# Schematic.net
KiCad netlist of a schematic drawn in EAGLE
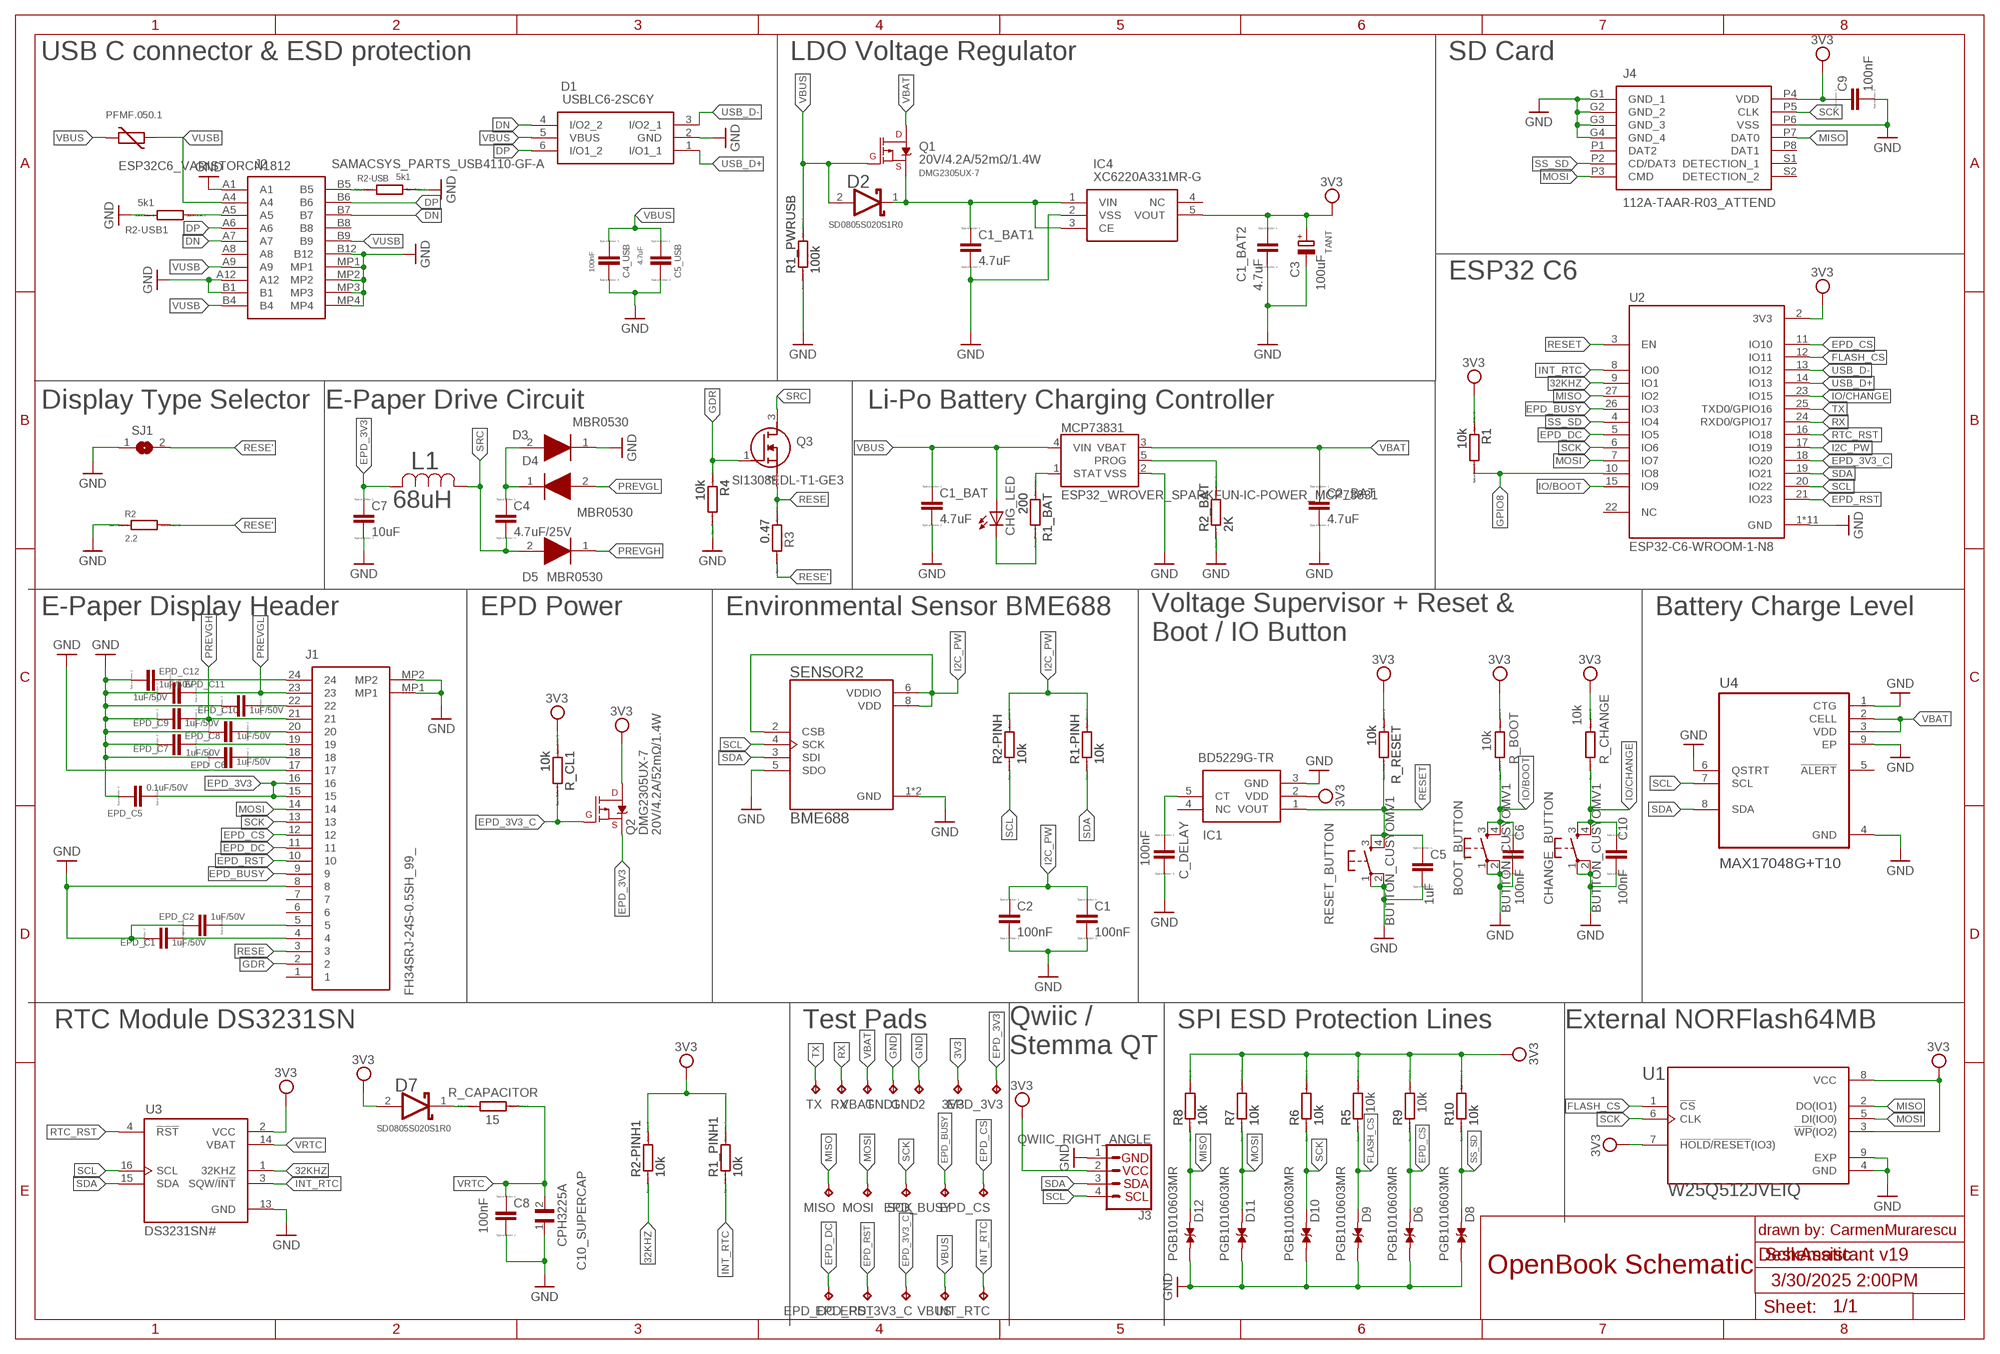
[diagram p0: schematic, sheet 1]

(export (version "E")
  (design (tool "Eeschema 10.0.6"))
  (components
    (comp (ref "3V3")
      (value "TPTP20R")
      (footprint "eagle-import:TP20R")
      (libsource (lib "eagle-import") (part "TPTP20R"))
    )
    (comp (ref "BOOT_BUTTON")
      (value "BUTTON_CUSYOMV1")
      (footprint "eagle-import:MYBUTTON")
      (libsource (lib "eagle-import") (part "BUTTON_CUSYOMV1"))
    )
    (comp (ref "C1")
      (value "100nF")
      (footprint "eagle-import:ESP32_WROVER_EAGLE-LTSPICE_C0402")
      (libsource (lib "eagle-import") (part "EAGLE-LTSPICE_CC0402"))
    )
    (comp (ref "C1_BAT")
      (value "4.7uF")
      (footprint "eagle-import:ESP32_WROVER_EAGLE-LTSPICE_C0402")
      (libsource (lib "eagle-import") (part "EAGLE-LTSPICE_CC0402"))
    )
    (comp (ref "C1_BAT1")
      (value "4.7uF")
      (footprint "eagle-import:ESP32_WROVER_EAGLE-LTSPICE_C0402")
      (libsource (lib "eagle-import") (part "ESP32_WROVER_EAGLE-LTSPICE_CC0402"))
    )
    (comp (ref "C1_BAT2")
      (value "4.7uF")
      (footprint "eagle-import:ESP32_WROVER_EAGLE-LTSPICE_C0402")
      (libsource (lib "eagle-import") (part "ESP32_WROVER_EAGLE-LTSPICE_CC0402"))
    )
    (comp (ref "C2")
      (value "100nF")
      (footprint "eagle-import:ESP32_WROVER_EAGLE-LTSPICE_C0402")
      (libsource (lib "eagle-import") (part "EAGLE-LTSPICE_CC0402"))
    )
    (comp (ref "C2_BAT")
      (value "4.7uF")
      (footprint "eagle-import:ESP32_WROVER_EAGLE-LTSPICE_C0402")
      (libsource (lib "eagle-import") (part "ESP32_WROVER_EAGLE-LTSPICE_CC0402"))
    )
    (comp (ref "C3")
      (value "100uF")
      (footprint "eagle-import:RCL_CT3528")
      (libsource (lib "eagle-import") (part "RCL_CPOL-EUCT3528"))
    )
    (comp (ref "C4")
      (value "4.7uF/25V")
      (footprint "eagle-import:ESP32_WROVER_EAGLE-LTSPICE_C0402")
      (libsource (lib "eagle-import") (part "EAGLE-LTSPICE_CC0402"))
    )
    (comp (ref "C4_USB")
      (value "100nF")
      (footprint "eagle-import:ESP32_WROVER_EAGLE-LTSPICE_C0402")
      (libsource (lib "eagle-import") (part "ESP32_WROVER_EAGLE-LTSPICE_CC0402"))
    )
    (comp (ref "C5")
      (value "1uF")
      (footprint "eagle-import:ESP32_WROVER_EAGLE-LTSPICE_C0402")
      (libsource (lib "eagle-import") (part "EAGLE-LTSPICE_CC0402"))
    )
    (comp (ref "C5_USB")
      (value "4.7uF")
      (footprint "eagle-import:ESP32_WROVER_EAGLE-LTSPICE_C0402")
      (libsource (lib "eagle-import") (part "ESP32_WROVER_EAGLE-LTSPICE_CC0402"))
    )
    (comp (ref "C6")
      (value "100nF")
      (footprint "eagle-import:ESP32_WROVER_EAGLE-LTSPICE_C0402")
      (libsource (lib "eagle-import") (part "ESP32_WROVER_EAGLE-LTSPICE_CC0402"))
    )
    (comp (ref "C7")
      (value "10uF")
      (footprint "eagle-import:ESP32_WROVER_EAGLE-LTSPICE_C0402")
      (libsource (lib "eagle-import") (part "ESP32_WROVER_EAGLE-LTSPICE_CC0402"))
    )
    (comp (ref "C8")
      (value "100nF")
      (footprint "eagle-import:ESP32_WROVER_EAGLE-LTSPICE_C0402")
      (libsource (lib "eagle-import") (part "ESP32_WROVER_EAGLE-LTSPICE_CC0402"))
    )
    (comp (ref "C9")
      (value "100nF")
      (footprint "eagle-import:ESP32_WROVER_EAGLE-LTSPICE_C0402")
      (libsource (lib "eagle-import") (part "EAGLE-LTSPICE_CC0402"))
    )
    (comp (ref "C10")
      (value "100nF")
      (footprint "eagle-import:ESP32_WROVER_EAGLE-LTSPICE_C0402")
      (libsource (lib "eagle-import") (part "ESP32_WROVER_EAGLE-LTSPICE_CC0402"))
    )
    (comp (ref "C10_SUPERCAP")
      (value "CPH3225A")
      (footprint "eagle-import:CAPCP3225X100N")
      (fields (field (name "MF") "Seiko Instruments"))
      (libsource (lib "eagle-import") (part "CPH3225A"))
    )
    (comp (ref "CHANGE_BUTTON")
      (value "BUTTON_CUSYOMV1")
      (footprint "eagle-import:MYBUTTON")
      (libsource (lib "eagle-import") (part "BUTTON_CUSYOMV1"))
    )
    (comp (ref "CHG_LED")
      (value "ADAFRUIT_LEDCHIP-LED0603")
      (footprint "eagle-import:ADAFRUIT_CHIP-LED0603")
      (libsource (lib "eagle-import") (part "ADAFRUIT_LEDCHIP-LED0603"))
    )
    (comp (ref "C_DELAY")
      (value "100nF")
      (footprint "eagle-import:ESP32_WROVER_EAGLE-LTSPICE_C0402")
      (libsource (lib "eagle-import") (part "EAGLE-LTSPICE_CC0402"))
    )
    (comp (ref "D1")
      (value "USBLC6-2SC6Y")
      (footprint "eagle-import:SOT95P280X145-6N")
      (fields (field (name "MF") "STMicroelectronics"))
      (libsource (lib "eagle-import") (part "USBLC6-2SC6Y"))
    )
    (comp (ref "D2")
      (value "ESP32_WROVER_AVX---SD0805S020S1R0_AVX_SD0805S020S1R0_0_0AVX_SD0805S020S1R0_0_0")
      (footprint "eagle-import:ESP32_WROVER_AVX---SD0805S020S1R0_AVX_SD0805S020S1R0_0")
      (fields
        (field (name "DIGIKEY_PART_NUMBER") "478-7800-1-ND")
        (field (name "MF") "AVX")
        (field (name "MOUSER_PART_NUMBER") "581-SD0805S020S1R0")
      )
      (libsource (lib "eagle-import") (part "ESP32_WROVER_AVX---SD0805S020S1R0_AVX_SD0805S020S1R0_0_0AVX_SD0805S020S1R0_0_0"))
    )
    (comp (ref "D3")
      (value "MBR0530")
      (footprint "eagle-import:SOD3716X135N")
      (fields (field (name "MF") "ON Semiconductor"))
      (libsource (lib "eagle-import") (part "MBR0530"))
    )
    (comp (ref "D4")
      (value "MBR0530")
      (footprint "eagle-import:SOD3716X135N")
      (fields (field (name "MF") "ON Semiconductor"))
      (libsource (lib "eagle-import") (part "MBR0530"))
    )
    (comp (ref "D5")
      (value "MBR0530")
      (footprint "eagle-import:SOD3716X135N")
      (fields (field (name "MF") "ON Semiconductor"))
      (libsource (lib "eagle-import") (part "MBR0530"))
    )
    (comp (ref "D6")
      (value "PGB1010603MR")
      (footprint "eagle-import:DIOC1608X36N")
      (fields (field (name "MF") "Littelfuse Inc."))
      (libsource (lib "eagle-import") (part "PGB1010603MR"))
    )
    (comp (ref "D7")
      (value "SD0805S020S1R0")
      (footprint "eagle-import:ESP32_WROVER_AVX---SD0805S020S1R0_AVX_SD0805S020S1R0_0")
      (fields
        (field (name "DIGIKEY_PART_NUMBER") "478-7800-1-ND")
        (field (name "MF") "AVX")
        (field (name "MOUSER_PART_NUMBER") "581-SD0805S020S1R0")
      )
      (libsource (lib "eagle-import") (part "ESP32_WROVER_AVX---SD0805S020S1R0_AVX_SD0805S020S1R0_0_0AVX_SD0805S020S1R0_0_0"))
    )
    (comp (ref "D8")
      (value "PGB1010603MR")
      (footprint "eagle-import:DIOC1608X36N")
      (fields (field (name "MF") "Littelfuse Inc."))
      (libsource (lib "eagle-import") (part "PGB1010603MR"))
    )
    (comp (ref "D9")
      (value "PGB1010603MR")
      (footprint "eagle-import:DIOC1608X36N")
      (fields (field (name "MF") "Littelfuse Inc."))
      (libsource (lib "eagle-import") (part "PGB1010603MR"))
    )
    (comp (ref "D10")
      (value "PGB1010603MR")
      (footprint "eagle-import:DIOC1608X36N")
      (fields (field (name "MF") "Littelfuse Inc."))
      (libsource (lib "eagle-import") (part "PGB1010603MR"))
    )
    (comp (ref "D11")
      (value "PGB1010603MR")
      (footprint "eagle-import:DIOC1608X36N")
      (fields (field (name "MF") "Littelfuse Inc."))
      (libsource (lib "eagle-import") (part "PGB1010603MR"))
    )
    (comp (ref "D12")
      (value "PGB1010603MR")
      (footprint "eagle-import:DIOC1608X36N")
      (fields (field (name "MF") "Littelfuse Inc."))
      (libsource (lib "eagle-import") (part "PGB1010603MR"))
    )
    (comp (ref "EPD_3V3")
      (value "TPTP20R")
      (footprint "eagle-import:TP20R")
      (libsource (lib "eagle-import") (part "TPTP20R"))
    )
    (comp (ref "EPD_3V3_C")
      (value "TPTP20R")
      (footprint "eagle-import:TP20R")
      (libsource (lib "eagle-import") (part "TPTP20R"))
    )
    (comp (ref "EPD_BUSY")
      (value "TPTP20R")
      (footprint "eagle-import:TP20R")
      (libsource (lib "eagle-import") (part "TPTP20R"))
    )
    (comp (ref "EPD_C1")
      (value "1uF/50V")
      (footprint "eagle-import:ESP32_WROVER_EAGLE-LTSPICE_C0402")
      (libsource (lib "eagle-import") (part "EAGLE-LTSPICE_CC0402"))
    )
    (comp (ref "EPD_C2")
      (value "1uF/50V")
      (footprint "eagle-import:ESP32_WROVER_EAGLE-LTSPICE_C0402")
      (libsource (lib "eagle-import") (part "EAGLE-LTSPICE_CC0402"))
    )
    (comp (ref "EPD_C5")
      (value "0.1uF/50V")
      (footprint "eagle-import:ESP32_WROVER_EAGLE-LTSPICE_C0402")
      (libsource (lib "eagle-import") (part "EAGLE-LTSPICE_CC0402"))
    )
    (comp (ref "EPD_C6")
      (value "1uF/50V")
      (footprint "eagle-import:ESP32_WROVER_EAGLE-LTSPICE_C0402")
      (libsource (lib "eagle-import") (part "EAGLE-LTSPICE_CC0402"))
    )
    (comp (ref "EPD_C7")
      (value "1uF/50V")
      (footprint "eagle-import:ESP32_WROVER_EAGLE-LTSPICE_C0402")
      (libsource (lib "eagle-import") (part "EAGLE-LTSPICE_CC0402"))
    )
    (comp (ref "EPD_C8")
      (value "1uF/50V")
      (footprint "eagle-import:ESP32_WROVER_EAGLE-LTSPICE_C0402")
      (libsource (lib "eagle-import") (part "EAGLE-LTSPICE_CC0402"))
    )
    (comp (ref "EPD_C9")
      (value "1uF/50V")
      (footprint "eagle-import:ESP32_WROVER_EAGLE-LTSPICE_C0402")
      (libsource (lib "eagle-import") (part "EAGLE-LTSPICE_CC0402"))
    )
    (comp (ref "EPD_C10")
      (value "1uF/50V")
      (footprint "eagle-import:ESP32_WROVER_EAGLE-LTSPICE_C0402")
      (libsource (lib "eagle-import") (part "EAGLE-LTSPICE_CC0402"))
    )
    (comp (ref "EPD_C11")
      (value "1uF/50V")
      (footprint "eagle-import:ESP32_WROVER_EAGLE-LTSPICE_C0402")
      (libsource (lib "eagle-import") (part "EAGLE-LTSPICE_CC0402"))
    )
    (comp (ref "EPD_C12")
      (value "1uF/50V")
      (footprint "eagle-import:ESP32_WROVER_EAGLE-LTSPICE_C0402")
      (libsource (lib "eagle-import") (part "EAGLE-LTSPICE_CC0402"))
    )
    (comp (ref "EPD_CS")
      (value "TPTP20R")
      (footprint "eagle-import:TP20R")
      (libsource (lib "eagle-import") (part "TPTP20R"))
    )
    (comp (ref "EPD_DC")
      (value "TPTP20R")
      (footprint "eagle-import:TP20R")
      (libsource (lib "eagle-import") (part "TPTP20R"))
    )
    (comp (ref "EPD_RST")
      (value "TPTP20R")
      (footprint "eagle-import:TP20R")
      (libsource (lib "eagle-import") (part "TPTP20R"))
    )
    (comp (ref "GND1")
      (value "TPTP20R")
      (footprint "eagle-import:TP20R")
      (libsource (lib "eagle-import") (part "TPTP20R"))
    )
    (comp (ref "GND2")
      (value "TPTP20R")
      (footprint "eagle-import:TP20R")
      (libsource (lib "eagle-import") (part "TPTP20R"))
    )
    (comp (ref "IC1")
      (value "BD5229G-TR")
      (footprint "eagle-import:SOT95P280X120-5N")
      (fields (field (name "MOUSER_PART_NUMBER") "755-BD5229G-TR"))
      (libsource (lib "eagle-import") (part "BD5229G-TR"))
    )
    (comp (ref "IC4")
      (value "XC6220A331MR-G")
      (footprint "eagle-import:SOT95P280X120-5N")
      (fields (field (name "MOUSER_PART_NUMBER") "865-XC6220A331MR-G"))
      (libsource (lib "eagle-import") (part "XC6220A331MR-G"))
    )
    (comp (ref "INT_RTC")
      (value "TPTP20R")
      (footprint "eagle-import:TP20R")
      (libsource (lib "eagle-import") (part "TPTP20R"))
    )
    (comp (ref "J1")
      (value "FH34SRJ-24S-0.5SH_99_")
      (footprint "eagle-import:FH34SRJ24S05SH99")
      (fields
        (field (name "MANUFACTURER_PART_NUMBER") "FH34SRJ-24S-0.5SH(99)")
        (field (name "MOUSER_PART_NUMBER") "798-FH34SRJ24S05SH99")
      )
      (libsource (lib "eagle-import") (part "FH34SRJ-24S-0.5SH_99_"))
    )
    (comp (ref "J2")
      (value "SAMACSYS_PARTS_USB4110-GF-A")
      (footprint "eagle-import:SAMACSYS_PARTS_USB4110GFA")
      (fields
        (field (name "MANUFACTURER_PART_NUMBER") "USB4110-GF-A")
        (field (name "MOUSER_PART_NUMBER") "640-USB4110-GF-A")
      )
      (libsource (lib "eagle-import") (part "SAMACSYS_PARTS_USB4110-GF-A"))
    )
    (comp (ref "J3")
      (value "QWIIC_RIGHT_ANGLE")
      (footprint "eagle-import:JST04_1MM_RA")
      (libsource (lib "eagle-import") (part "QWIIC_CONNECTORJS-1MM"))
    )
    (comp (ref "J4")
      (value "112A-TAAR-R03_ATTEND")
      (footprint "eagle-import:112ATAARR03ATTEND")
      (fields (field (name "MANUFACTURER_PART_NUMBER") "112A-TAAR-R03 ATTEND"))
      (libsource (lib "eagle-import") (part "112A-TAAR-R03_ATTEND"))
    )
    (comp (ref "L1")
      (value "68uH")
      (footprint "eagle-import:IND_4828-WE-TPC_WRE")
      (fields
        (field (name "MANUFACTURER_PART_NUMBER") "744043680")
        (field (name "COPYRIGHT") "Copyright (C) 2024 Ultra Librarian. All rights reserved.")
      )
      (libsource (lib "eagle-import") (part "744043680IND_4828-WE-TPC_WRE"))
    )
    (comp (ref "MCP73831")
      (value "ESP32_WROVER_SPARKFUN-IC-POWER_MCP73831")
      (footprint "eagle-import:ESP32_WROVER_SPARKFUN-IC-POWER_SOT23-5")
      (libsource (lib "eagle-import") (part "ESP32_WROVER_SPARKFUN-IC-POWER_MCP73831"))
    )
    (comp (ref "MISO")
      (value "TPTP20R")
      (footprint "eagle-import:TP20R")
      (libsource (lib "eagle-import") (part "TPTP20R"))
    )
    (comp (ref "MOSI")
      (value "TPTP20R")
      (footprint "eagle-import:TP20R")
      (libsource (lib "eagle-import") (part "TPTP20R"))
    )
    (comp (ref "PFMF.050.1")
      (value "ESP32C6_VARISTORCN1812")
      (footprint "eagle-import:ESP32C6_VARISTOR_CT_CN1812")
      (libsource (lib "eagle-import") (part "ESP32C6_VARISTORCN1812"))
    )
    (comp (ref "Q1")
      (value "20V/4.2A/52mΩ/1.4W")
      (footprint "eagle-import:ESP32_WROVER_SPARKFUN-DISCRETESEMI_SOT23-3")
      (libsource (lib "eagle-import") (part "ESP32_WROVER_SPARKFUN-DISCRETESEMI_MOSFET_PCH-DMG2305UX-7"))
    )
    (comp (ref "Q2")
      (value "20V/4.2A/52mΩ/1.4W")
      (footprint "eagle-import:ESP32_WROVER_SPARKFUN-DISCRETESEMI_SOT23-3")
      (libsource (lib "eagle-import") (part "ESP32_WROVER_SPARKFUN-DISCRETESEMI_MOSFET_PCH-DMG2305UX-7"))
    )
    (comp (ref "Q3")
      (value "SI1308EDL-T1-GE3")
      (footprint "eagle-import:SOT65P210X110-3N")
      (fields (field (name "MF") "Vishay Siliconix"))
      (libsource (lib "eagle-import") (part "SI1308EDL-T1-GE3"))
    )
    (comp (ref "R1")
      (value "10k")
      (footprint "eagle-import:ESP32_WROVER_EAGLE-LTSPICE_R0402")
      (libsource (lib "eagle-import") (part "ESP32_WROVER_EAGLE-LTSPICE_RR0402"))
    )
    (comp (ref "R1-PINH")
      (value "10k")
      (footprint "eagle-import:ESP32_WROVER_EAGLE-LTSPICE_R0402")
      (libsource (lib "eagle-import") (part "ESP32_WROVER_EAGLE-LTSPICE_RR0402"))
    )
    (comp (ref "R1_BAT")
      (value "200")
      (footprint "eagle-import:ESP32_WROVER_EAGLE-LTSPICE_R0402")
      (libsource (lib "eagle-import") (part "ESP32_WROVER_EAGLE-LTSPICE_RR0402"))
    )
    (comp (ref "R1_PINH1")
      (value "10k")
      (footprint "eagle-import:ESP32_WROVER_EAGLE-LTSPICE_R0402")
      (libsource (lib "eagle-import") (part "ESP32_WROVER_EAGLE-LTSPICE_RR0402"))
    )
    (comp (ref "R1_PWRUSB")
      (value "100k")
      (footprint "eagle-import:ESP32_WROVER_EAGLE-LTSPICE_R0402")
      (libsource (lib "eagle-import") (part "ESP32_WROVER_EAGLE-LTSPICE_RR0402"))
    )
    (comp (ref "R2")
      (value "2.2")
      (footprint "eagle-import:ESP32_WROVER_EAGLE-LTSPICE_R0402")
      (libsource (lib "eagle-import") (part "ESP32_WROVER_EAGLE-LTSPICE_RR0402"))
    )
    (comp (ref "R2-PINH")
      (value "10k")
      (footprint "eagle-import:ESP32_WROVER_EAGLE-LTSPICE_R0402")
      (libsource (lib "eagle-import") (part "ESP32_WROVER_EAGLE-LTSPICE_RR0402"))
    )
    (comp (ref "R2-PINH1")
      (value "10k")
      (footprint "eagle-import:ESP32_WROVER_EAGLE-LTSPICE_R0402")
      (libsource (lib "eagle-import") (part "ESP32_WROVER_EAGLE-LTSPICE_RR0402"))
    )
    (comp (ref "R2-USB")
      (value "5k1")
      (footprint "eagle-import:ESP32_WROVER_EAGLE-LTSPICE_R0402")
      (libsource (lib "eagle-import") (part "ESP32_WROVER_EAGLE-LTSPICE_RR0402"))
    )
    (comp (ref "R2-USB1")
      (value "5k1")
      (footprint "eagle-import:ESP32_WROVER_EAGLE-LTSPICE_R0402")
      (libsource (lib "eagle-import") (part "ESP32_WROVER_EAGLE-LTSPICE_RR0402"))
    )
    (comp (ref "R2_BAT")
      (value "2K")
      (footprint "eagle-import:ESP32_WROVER_EAGLE-LTSPICE_R0402")
      (libsource (lib "eagle-import") (part "ESP32_WROVER_EAGLE-LTSPICE_RR0402"))
    )
    (comp (ref "R3")
      (value "0.47")
      (footprint "eagle-import:ESP32_WROVER_EAGLE-LTSPICE_R0402")
      (libsource (lib "eagle-import") (part "ESP32_WROVER_EAGLE-LTSPICE_RR0402"))
    )
    (comp (ref "R4")
      (value "10k")
      (footprint "eagle-import:ESP32_WROVER_EAGLE-LTSPICE_R0402")
      (libsource (lib "eagle-import") (part "ESP32_WROVER_EAGLE-LTSPICE_RR0402"))
    )
    (comp (ref "R5")
      (value "10k")
      (footprint "eagle-import:ESP32_WROVER_EAGLE-LTSPICE_R0402")
      (libsource (lib "eagle-import") (part "ESP32_WROVER_EAGLE-LTSPICE_RR0402"))
    )
    (comp (ref "R6")
      (value "10k")
      (footprint "eagle-import:ESP32_WROVER_EAGLE-LTSPICE_R0402")
      (libsource (lib "eagle-import") (part "ESP32_WROVER_EAGLE-LTSPICE_RR0402"))
    )
    (comp (ref "R7")
      (value "10k")
      (footprint "eagle-import:ESP32_WROVER_EAGLE-LTSPICE_R0402")
      (libsource (lib "eagle-import") (part "ESP32_WROVER_EAGLE-LTSPICE_RR0402"))
    )
    (comp (ref "R8")
      (value "10k")
      (footprint "eagle-import:ESP32_WROVER_EAGLE-LTSPICE_R0402")
      (libsource (lib "eagle-import") (part "ESP32_WROVER_EAGLE-LTSPICE_RR0402"))
    )
    (comp (ref "R9")
      (value "10k")
      (footprint "eagle-import:ESP32_WROVER_EAGLE-LTSPICE_R0402")
      (libsource (lib "eagle-import") (part "ESP32_WROVER_EAGLE-LTSPICE_RR0402"))
    )
    (comp (ref "R10")
      (value "10k")
      (footprint "eagle-import:ESP32_WROVER_EAGLE-LTSPICE_R0402")
      (libsource (lib "eagle-import") (part "ESP32_WROVER_EAGLE-LTSPICE_RR0402"))
    )
    (comp (ref "RESET_BUTTON")
      (value "BUTTON_CUSYOMV1")
      (footprint "eagle-import:MYBUTTON")
      (libsource (lib "eagle-import") (part "BUTTON_CUSYOMV1"))
    )
    (comp (ref "RX")
      (value "TPTP20R")
      (footprint "eagle-import:TP20R")
      (libsource (lib "eagle-import") (part "TPTP20R"))
    )
    (comp (ref "R_BOOT")
      (value "10k")
      (footprint "eagle-import:ESP32_WROVER_EAGLE-LTSPICE_R0402")
      (libsource (lib "eagle-import") (part "ESP32_WROVER_EAGLE-LTSPICE_RR0402"))
    )
    (comp (ref "R_CAPACITOR")
      (value "15")
      (footprint "eagle-import:ESP32_WROVER_EAGLE-LTSPICE_R0402")
      (libsource (lib "eagle-import") (part "ESP32_WROVER_EAGLE-LTSPICE_RR0402"))
    )
    (comp (ref "R_CHANGE")
      (value "10k")
      (footprint "eagle-import:ESP32_WROVER_EAGLE-LTSPICE_R0402")
      (libsource (lib "eagle-import") (part "ESP32_WROVER_EAGLE-LTSPICE_RR0402"))
    )
    (comp (ref "R_CL1")
      (value "10k")
      (footprint "eagle-import:ESP32_WROVER_EAGLE-LTSPICE_R0402")
      (libsource (lib "eagle-import") (part "ESP32_WROVER_EAGLE-LTSPICE_RR0402"))
    )
    (comp (ref "R_RESET")
      (value "10k")
      (footprint "eagle-import:ESP32_WROVER_EAGLE-LTSPICE_R0402")
      (libsource (lib "eagle-import") (part "ESP32_WROVER_EAGLE-LTSPICE_RR0402"))
    )
    (comp (ref "SCK")
      (value "TPTP20R")
      (footprint "eagle-import:TP20R")
      (libsource (lib "eagle-import") (part "TPTP20R"))
    )
    (comp (ref "SENSOR2")
      (value "BME688")
      (footprint "eagle-import:ESP32_WROVER_BME680_PSON80P300X300X100-8N")
      (fields (field (name "MF") "Bosch Sensortec") (field (name "MP") "BME680"))
      (libsource (lib "eagle-import") (part "ESP32_WROVER_BME680_BME680"))
    )
    (comp (ref "SJ1") (value "SJ") (footprint "eagle-import:SJ") (libsource (lib "eagle-import") (part "SJ")))
    (comp (ref "TX")
      (value "TPTP20R")
      (footprint "eagle-import:TP20R")
      (libsource (lib "eagle-import") (part "TPTP20R"))
    )
    (comp (ref "U1")
      (value "W25Q512JVEIQ")
      (footprint "eagle-import:SON127P600X800X80-9N")
      (fields (field (name "MF") "Winbond Electronics"))
      (libsource (lib "eagle-import") (part "W25Q512JVEIQ"))
    )
    (comp (ref "U2")
      (value "ESP32-C6-WROOM-1-N8")
      (footprint "eagle-import:XCVR_ESP32-C6-WROOM-1-N8")
      (fields (field (name "MF") "Espressif Systems"))
      (libsource (lib "eagle-import") (part "ESP32-C6-WROOM-1-N8"))
    )
    (comp (ref "U3")
      (value "DS3231SN#")
      (footprint "eagle-import:SOIC127P1032X265-16N")
      (fields (field (name "MF") "Analog Devices"))
      (libsource (lib "eagle-import") (part "DS3231SN#"))
    )
    (comp (ref "U4")
      (value "MAX17048G+T10")
      (footprint "eagle-import:SON50P200X200X80-9N")
      (fields (field (name "MF") "Analog Devices"))
      (libsource (lib "eagle-import") (part "MAX17048G+T10"))
    )
    (comp (ref "VBAT")
      (value "TPTP20R")
      (footprint "eagle-import:TP20R")
      (libsource (lib "eagle-import") (part "TPTP20R"))
    )
    (comp (ref "VBUS")
      (value "TPTP20R")
      (footprint "eagle-import:TP20R")
      (libsource (lib "eagle-import") (part "TPTP20R"))
    )
  )
  (nets
    (net (code "1") (name "3V3") (class "Default")
      (node (ref "3V3") (pin "TP") (pinfunction "TP_TP") (pintype "input"))
      (node (ref "C1_BAT2") (pin "1") (pinfunction "1_1") (pintype "passive"))
      (node (ref "C3") (pin "+") (pinfunction "+_+") (pintype "passive"))
      (node (ref "C9") (pin "1") (pinfunction "1_1") (pintype "passive"))
      (node (ref "D7") (pin "2") (pinfunction "ANODE_2") (pintype "bidirectional"))
      (node (ref "IC1") (pin "2") (pinfunction "VDD_2") (pintype "bidirectional"))
      (node (ref "IC4") (pin "5") (pinfunction "VOUT_5") (pintype "bidirectional"))
      (node (ref "J3") (pin "2") (pinfunction "2_2") (pintype "power_in"))
      (node (ref "J4") (pin "P4") (pinfunction "VDD_P4") (pintype "bidirectional"))
      (node (ref "Q2") (pin "3") (pinfunction "D_3") (pintype "bidirectional"))
      (node (ref "R1") (pin "1") (pinfunction "1_1") (pintype "passive"))
      (node (ref "R10") (pin "2") (pinfunction "2_2") (pintype "passive"))
      (node (ref "R1_PINH1") (pin "2") (pinfunction "2_2") (pintype "passive"))
      (node (ref "R2-PINH1") (pin "2") (pinfunction "2_2") (pintype "passive"))
      (node (ref "R5") (pin "2") (pinfunction "2_2") (pintype "passive"))
      (node (ref "R6") (pin "2") (pinfunction "2_2") (pintype "passive"))
      (node (ref "R7") (pin "2") (pinfunction "2_2") (pintype "passive"))
      (node (ref "R8") (pin "2") (pinfunction "2_2") (pintype "passive"))
      (node (ref "R9") (pin "2") (pinfunction "2_2") (pintype "passive"))
      (node (ref "R_BOOT") (pin "2") (pinfunction "2_2") (pintype "passive"))
      (node (ref "R_CHANGE") (pin "2") (pinfunction "2_2") (pintype "passive"))
      (node (ref "R_CL1") (pin "1") (pinfunction "1_1") (pintype "passive"))
      (node (ref "R_RESET") (pin "1") (pinfunction "1_1") (pintype "passive"))
      (node (ref "U1") (pin "3") (pinfunction "~{WP}(IO2)_3") (pintype "bidirectional"))
      (node (ref "U1") (pin "7") (pinfunction "~{HOLD}/~{RESET}(IO3)_7") (pintype "bidirectional"))
      (node (ref "U1") (pin "8") (pinfunction "VCC_8") (pintype "power_in"))
      (node (ref "U2") (pin "2") (pinfunction "3V3_2") (pintype "power_in"))
      (node (ref "U3") (pin "2") (pinfunction "VCC_2") (pintype "power_in"))
    )
    (net (code "2") (name "32KHZ") (class "Default")
      (node (ref "R2-PINH1") (pin "1") (pinfunction "1_1") (pintype "passive"))
      (node (ref "U2") (pin "9") (pinfunction "IO1_9") (pintype "bidirectional"))
      (node (ref "U3") (pin "1") (pinfunction "32KHZ_1") (pintype "output"))
    )
    (net (code "3") (name "DN") (class "Default")
      (node (ref "D1") (pin "4") (pinfunction "I/O2_2_4") (pintype "bidirectional"))
      (node (ref "J2") (pin "A7") (pinfunction "A7_A7") (pintype "bidirectional"))
      (node (ref "J2") (pin "B7") (pinfunction "B7_B7") (pintype "bidirectional"))
    )
    (net (code "4") (name "DP") (class "Default")
      (node (ref "D1") (pin "6") (pinfunction "I/O1_2_6") (pintype "bidirectional"))
      (node (ref "J2") (pin "A6") (pinfunction "A6_A6") (pintype "bidirectional"))
      (node (ref "J2") (pin "B6") (pinfunction "B6_B6") (pintype "bidirectional"))
    )
    (net (code "5") (name "EPD_3V3") (class "Default")
      (node (ref "C7") (pin "1") (pinfunction "1_1") (pintype "passive"))
      (node (ref "EPD_3V3") (pin "TP") (pinfunction "TP_TP") (pintype "input"))
      (node (ref "EPD_C5") (pin "1") (pinfunction "1_1") (pintype "passive"))
      (node (ref "J1") (pin "15") (pinfunction "15_15") (pintype "bidirectional"))
      (node (ref "J1") (pin "16") (pinfunction "16_16") (pintype "bidirectional"))
      (node (ref "L1") (pin "2") (pinfunction "2_2") (pintype "passive"))
      (node (ref "Q2") (pin "2") (pinfunction "S_2") (pintype "bidirectional"))
    )
    (net (code "6") (name "EPD_3V3_C") (class "Default")
      (node (ref "EPD_3V3_C") (pin "TP") (pinfunction "TP_TP") (pintype "input"))
      (node (ref "Q2") (pin "1") (pinfunction "G_1") (pintype "bidirectional"))
      (node (ref "R_CL1") (pin "2") (pinfunction "2_2") (pintype "passive"))
      (node (ref "U2") (pin "18") (pinfunction "IO20_18") (pintype "bidirectional"))
    )
    (net (code "7") (name "EPD_BUSY") (class "Default")
      (node (ref "EPD_BUSY") (pin "TP") (pinfunction "TP_TP") (pintype "input"))
      (node (ref "J1") (pin "9") (pinfunction "9_9") (pintype "bidirectional"))
      (node (ref "U2") (pin "26") (pinfunction "IO3_26") (pintype "bidirectional"))
    )
    (net (code "8") (name "EPD_CS") (class "Default")
      (node (ref "D6") (pin "2") (pinfunction "2_2") (pintype "passive"))
      (node (ref "EPD_CS") (pin "TP") (pinfunction "TP_TP") (pintype "input"))
      (node (ref "J1") (pin "12") (pinfunction "12_12") (pintype "bidirectional"))
      (node (ref "R9") (pin "1") (pinfunction "1_1") (pintype "passive"))
      (node (ref "U2") (pin "11") (pinfunction "IO10_11") (pintype "bidirectional"))
    )
    (net (code "9") (name "EPD_DC") (class "Default")
      (node (ref "EPD_DC") (pin "TP") (pinfunction "TP_TP") (pintype "input"))
      (node (ref "J1") (pin "11") (pinfunction "11_11") (pintype "bidirectional"))
      (node (ref "U2") (pin "5") (pinfunction "IO5_5") (pintype "bidirectional"))
    )
    (net (code "10") (name "EPD_RST") (class "Default")
      (node (ref "EPD_RST") (pin "TP") (pinfunction "TP_TP") (pintype "input"))
      (node (ref "J1") (pin "10") (pinfunction "10_10") (pintype "bidirectional"))
      (node (ref "U2") (pin "21") (pinfunction "IO23_21") (pintype "bidirectional"))
    )
    (net (code "11") (name "FLASH_CS") (class "Default")
      (node (ref "D9") (pin "2") (pinfunction "2_2") (pintype "passive"))
      (node (ref "R5") (pin "1") (pinfunction "1_1") (pintype "passive"))
      (node (ref "U1") (pin "1") (pinfunction "~{CS}_1") (pintype "input"))
      (node (ref "U2") (pin "12") (pinfunction "IO11_12") (pintype "bidirectional"))
    )
    (net (code "12") (name "GDR") (class "Default")
      (node (ref "J1") (pin "2") (pinfunction "2_2") (pintype "bidirectional"))
      (node (ref "Q3") (pin "1") (pinfunction "G_1") (pintype "bidirectional"))
      (node (ref "R4") (pin "1") (pinfunction "1_1") (pintype "passive"))
    )
    (net (code "13") (name "GND") (class "Default")
      (node (ref "BOOT_BUTTON") (pin "1") (pinfunction "1_1") (pintype "passive"))
      (node (ref "BOOT_BUTTON") (pin "2") (pinfunction "2_2") (pintype "passive"))
      (node (ref "C1") (pin "2") (pinfunction "2_2") (pintype "passive"))
      (node (ref "C10") (pin "2") (pinfunction "2_2") (pintype "passive"))
      (node (ref "C10_SUPERCAP") (pin "1") (pinfunction "1_1") (pintype "passive"))
      (node (ref "C1_BAT") (pin "2") (pinfunction "2_2") (pintype "passive"))
      (node (ref "C1_BAT1") (pin "2") (pinfunction "2_2") (pintype "passive"))
      (node (ref "C1_BAT2") (pin "2") (pinfunction "2_2") (pintype "passive"))
      (node (ref "C2") (pin "2") (pinfunction "2_2") (pintype "passive"))
      (node (ref "C2_BAT") (pin "2") (pinfunction "2_2") (pintype "passive"))
      (node (ref "C3") (pin "-") (pinfunction "-_-") (pintype "passive"))
      (node (ref "C4_USB") (pin "2") (pinfunction "2_2") (pintype "passive"))
      (node (ref "C5") (pin "2") (pinfunction "2_2") (pintype "passive"))
      (node (ref "C5_USB") (pin "2") (pinfunction "2_2") (pintype "passive"))
      (node (ref "C6") (pin "2") (pinfunction "2_2") (pintype "passive"))
      (node (ref "C7") (pin "2") (pinfunction "2_2") (pintype "passive"))
      (node (ref "C8") (pin "2") (pinfunction "2_2") (pintype "passive"))
      (node (ref "C9") (pin "2") (pinfunction "2_2") (pintype "passive"))
      (node (ref "CHANGE_BUTTON") (pin "1") (pinfunction "1_1") (pintype "passive"))
      (node (ref "CHANGE_BUTTON") (pin "2") (pinfunction "2_2") (pintype "passive"))
      (node (ref "C_DELAY") (pin "2") (pinfunction "2_2") (pintype "passive"))
      (node (ref "D1") (pin "2") (pinfunction "GND_2") (pintype "bidirectional"))
      (node (ref "D10") (pin "1") (pinfunction "1_1") (pintype "passive"))
      (node (ref "D11") (pin "1") (pinfunction "1_1") (pintype "passive"))
      (node (ref "D12") (pin "1") (pinfunction "1_1") (pintype "passive"))
      (node (ref "D4") (pin "1") (pinfunction "K_1") (pintype "bidirectional"))
      (node (ref "D6") (pin "1") (pinfunction "1_1") (pintype "passive"))
      (node (ref "D8") (pin "1") (pinfunction "1_1") (pintype "passive"))
      (node (ref "D9") (pin "1") (pinfunction "1_1") (pintype "passive"))
      (node (ref "EPD_C1") (pin "2") (pinfunction "2_2") (pintype "passive"))
      (node (ref "EPD_C10") (pin "2") (pinfunction "2_2") (pintype "passive"))
      (node (ref "EPD_C11") (pin "2") (pinfunction "2_2") (pintype "passive"))
      (node (ref "EPD_C12") (pin "2") (pinfunction "2_2") (pintype "passive"))
      (node (ref "EPD_C2") (pin "2") (pinfunction "2_2") (pintype "passive"))
      (node (ref "EPD_C5") (pin "2") (pinfunction "2_2") (pintype "passive"))
      (node (ref "EPD_C6") (pin "2") (pinfunction "2_2") (pintype "passive"))
      (node (ref "EPD_C7") (pin "2") (pinfunction "2_2") (pintype "passive"))
      (node (ref "EPD_C8") (pin "2") (pinfunction "2_2") (pintype "passive"))
      (node (ref "EPD_C9") (pin "2") (pinfunction "2_2") (pintype "passive"))
      (node (ref "GND1") (pin "TP") (pinfunction "TP_TP") (pintype "input"))
      (node (ref "GND2") (pin "TP") (pinfunction "TP_TP") (pintype "input"))
      (node (ref "IC1") (pin "3") (pinfunction "GND_3") (pintype "bidirectional"))
      (node (ref "IC4") (pin "2") (pinfunction "VSS_2") (pintype "bidirectional"))
      (node (ref "J1") (pin "17") (pinfunction "17_17") (pintype "bidirectional"))
      (node (ref "J1") (pin "8") (pinfunction "8_8") (pintype "bidirectional"))
      (node (ref "J1") (pin "MP1") (pinfunction "MP1_MP1") (pintype "bidirectional"))
      (node (ref "J1") (pin "MP2") (pinfunction "MP2_MP2") (pintype "bidirectional"))
      (node (ref "J2") (pin "A1") (pinfunction "A1_A1") (pintype "bidirectional"))
      (node (ref "J2") (pin "A12") (pinfunction "A12_A12") (pintype "bidirectional"))
      (node (ref "J2") (pin "B1") (pinfunction "B1_B1") (pintype "bidirectional"))
      (node (ref "J2") (pin "B12") (pinfunction "B12_B12") (pintype "bidirectional"))
      (node (ref "J2") (pin "MP1") (pinfunction "MP1_MP1") (pintype "bidirectional"))
      (node (ref "J2") (pin "MP2") (pinfunction "MP2_MP2") (pintype "bidirectional"))
      (node (ref "J2") (pin "MP3") (pinfunction "MP3_MP3") (pintype "bidirectional"))
      (node (ref "J2") (pin "MP4") (pinfunction "MP4_MP4") (pintype "bidirectional"))
      (node (ref "J3") (pin "1") (pinfunction "1_1") (pintype "power_in"))
      (node (ref "J4") (pin "G1") (pinfunction "GND_1_G1") (pintype "bidirectional"))
      (node (ref "J4") (pin "G2") (pinfunction "GND_2_G2") (pintype "bidirectional"))
      (node (ref "J4") (pin "G3") (pinfunction "GND_3_G3") (pintype "bidirectional"))
      (node (ref "J4") (pin "G4") (pinfunction "GND_4_G4") (pintype "bidirectional"))
      (node (ref "J4") (pin "P6") (pinfunction "VSS_P6") (pintype "bidirectional"))
      (node (ref "MCP73831") (pin "2") (pinfunction "VSS_2") (pintype "power_in"))
      (node (ref "R1_PWRUSB") (pin "1") (pinfunction "1_1") (pintype "passive"))
      (node (ref "R2") (pin "1") (pinfunction "1_1") (pintype "passive"))
      (node (ref "R2-USB") (pin "2") (pinfunction "2_2") (pintype "passive"))
      (node (ref "R2-USB1") (pin "1") (pinfunction "1_1") (pintype "passive"))
      (node (ref "R2_BAT") (pin "1") (pinfunction "1_1") (pintype "passive"))
      (node (ref "R4") (pin "2") (pinfunction "2_2") (pintype "passive"))
      (node (ref "RESET_BUTTON") (pin "1") (pinfunction "1_1") (pintype "passive"))
      (node (ref "RESET_BUTTON") (pin "2") (pinfunction "2_2") (pintype "passive"))
      (node (ref "SENSOR2") (pin "1") (pinfunction "GND_1") (pintype "power_in"))
      (node (ref "SENSOR2") (pin "5") (pinfunction "SDO_5") (pintype "bidirectional"))
      (node (ref "SENSOR2") (pin "7") (pinfunction "GND_7") (pintype "power_in"))
      (node (ref "SJ1") (pin "1") (pinfunction "1_1") (pintype "passive"))
      (node (ref "U1") (pin "4") (pinfunction "GND_4") (pintype "power_in"))
      (node (ref "U1") (pin "9") (pinfunction "EXP_9") (pintype "passive"))
      (node (ref "U2") (pin "1") (pinfunction "GND_1") (pintype "power_in"))
      (node (ref "U2") (pin "28") (pinfunction "GND_28") (pintype "power_in"))
      (node (ref "U2") (pin "29_1") (pinfunction "GND_29_1") (pintype "power_in"))
      (node (ref "U2") (pin "29_2") (pinfunction "GND_29_2") (pintype "power_in"))
      (node (ref "U2") (pin "29_3") (pinfunction "GND_29_3") (pintype "power_in"))
      (node (ref "U2") (pin "29_4") (pinfunction "GND_29_4") (pintype "power_in"))
      (node (ref "U2") (pin "29_5") (pinfunction "GND_29_5") (pintype "power_in"))
      (node (ref "U2") (pin "29_6") (pinfunction "GND_29_6") (pintype "power_in"))
      (node (ref "U2") (pin "29_7") (pinfunction "GND_29_7") (pintype "power_in"))
      (node (ref "U2") (pin "29_8") (pinfunction "GND_29_8") (pintype "power_in"))
      (node (ref "U2") (pin "29_9") (pinfunction "GND_29_9") (pintype "power_in"))
      (node (ref "U3") (pin "13") (pinfunction "GND_13") (pintype "power_in"))
      (node (ref "U4") (pin "1") (pinfunction "CTG_1") (pintype "power_in"))
      (node (ref "U4") (pin "4") (pinfunction "GND_4") (pintype "power_in"))
      (node (ref "U4") (pin "6") (pinfunction "QSTRT_6") (pintype "input"))
      (node (ref "U4") (pin "9") (pinfunction "EP_9") (pintype "power_in"))
    )
    (net (code "14") (name "GPIO8") (class "Default")
      (node (ref "R1") (pin "2") (pinfunction "2_2") (pintype "passive"))
      (node (ref "U2") (pin "10") (pinfunction "IO8_10") (pintype "bidirectional"))
    )
    (net (code "15") (name "I2C_PW") (class "Default")
      (node (ref "C1") (pin "1") (pinfunction "1_1") (pintype "passive"))
      (node (ref "C2") (pin "1") (pinfunction "1_1") (pintype "passive"))
      (node (ref "R1-PINH") (pin "2") (pinfunction "2_2") (pintype "passive"))
      (node (ref "R2-PINH") (pin "2") (pinfunction "2_2") (pintype "passive"))
      (node (ref "SENSOR2") (pin "2") (pinfunction "CSB_2") (pintype "input"))
      (node (ref "SENSOR2") (pin "6") (pinfunction "VDDIO_6") (pintype "power_in"))
      (node (ref "SENSOR2") (pin "8") (pinfunction "VDD_8") (pintype "power_in"))
      (node (ref "U2") (pin "17") (pinfunction "IO19_17") (pintype "bidirectional"))
    )
    (net (code "16") (name "INT_RTC") (class "Default")
      (node (ref "INT_RTC") (pin "TP") (pinfunction "TP_TP") (pintype "input"))
      (node (ref "R1_PINH1") (pin "1") (pinfunction "1_1") (pintype "passive"))
      (node (ref "U2") (pin "8") (pinfunction "IO0_8") (pintype "bidirectional"))
      (node (ref "U3") (pin "3") (pinfunction "SQW/~{INT}_3") (pintype "output"))
    )
    (net (code "17") (name "IO{slash}BOOT") (class "Default")
      (node (ref "BOOT_BUTTON") (pin "3") (pinfunction "3_3") (pintype "passive"))
      (node (ref "BOOT_BUTTON") (pin "4") (pinfunction "4_4") (pintype "passive"))
      (node (ref "C6") (pin "1") (pinfunction "1_1") (pintype "passive"))
      (node (ref "R_BOOT") (pin "1") (pinfunction "1_1") (pintype "passive"))
      (node (ref "U2") (pin "15") (pinfunction "IO9_15") (pintype "bidirectional"))
    )
    (net (code "18") (name "IO{slash}CHANGE") (class "Default")
      (node (ref "C10") (pin "1") (pinfunction "1_1") (pintype "passive"))
      (node (ref "CHANGE_BUTTON") (pin "3") (pinfunction "3_3") (pintype "passive"))
      (node (ref "CHANGE_BUTTON") (pin "4") (pinfunction "4_4") (pintype "passive"))
      (node (ref "R_CHANGE") (pin "1") (pinfunction "1_1") (pintype "passive"))
      (node (ref "U2") (pin "23") (pinfunction "IO15_23") (pintype "bidirectional"))
    )
    (net (code "19") (name "MISO") (class "Default")
      (node (ref "D12") (pin "2") (pinfunction "2_2") (pintype "passive"))
      (node (ref "J4") (pin "P7") (pinfunction "DAT0_P7") (pintype "bidirectional"))
      (node (ref "MISO") (pin "TP") (pinfunction "TP_TP") (pintype "input"))
      (node (ref "R8") (pin "1") (pinfunction "1_1") (pintype "passive"))
      (node (ref "U1") (pin "2") (pinfunction "DO(IO1)_2") (pintype "bidirectional"))
      (node (ref "U2") (pin "27") (pinfunction "IO2_27") (pintype "bidirectional"))
    )
    (net (code "20") (name "MOSI") (class "Default")
      (node (ref "D11") (pin "2") (pinfunction "2_2") (pintype "passive"))
      (node (ref "J1") (pin "14") (pinfunction "14_14") (pintype "bidirectional"))
      (node (ref "J4") (pin "P3") (pinfunction "CMD_P3") (pintype "bidirectional"))
      (node (ref "MOSI") (pin "TP") (pinfunction "TP_TP") (pintype "input"))
      (node (ref "R7") (pin "1") (pinfunction "1_1") (pintype "passive"))
      (node (ref "U1") (pin "5") (pinfunction "DI(IO0)_5") (pintype "bidirectional"))
      (node (ref "U2") (pin "7") (pinfunction "IO7_7") (pintype "bidirectional"))
    )
    (net (code "21") (name "Net-(CHG_LED-PadC)") (class "Default")
      (node (ref "CHG_LED") (pin "C") (pinfunction "C_C") (pintype "passive"))
      (node (ref "R1_BAT") (pin "2") (pinfunction "2_2") (pintype "passive"))
    )
    (net (code "22") (name "Net-(D2-CATHODE)") (class "Default")
      (node (ref "C1_BAT1") (pin "1") (pinfunction "1_1") (pintype "passive"))
      (node (ref "D2") (pin "1") (pinfunction "CATHODE_1") (pintype "bidirectional"))
      (node (ref "IC4") (pin "1") (pinfunction "VIN_1") (pintype "bidirectional"))
      (node (ref "IC4") (pin "3") (pinfunction "CE_3") (pintype "bidirectional"))
      (node (ref "Q1") (pin "2") (pinfunction "S_2") (pintype "bidirectional"))
    )
    (net (code "23") (name "Net-(D3-K)") (class "Default")
      (node (ref "C4") (pin "1") (pinfunction "1_1") (pintype "passive"))
      (node (ref "D3") (pin "1") (pinfunction "K_1") (pintype "bidirectional"))
      (node (ref "D4") (pin "2") (pinfunction "A_2") (pintype "bidirectional"))
    )
    (net (code "24") (name "Net-(D7-CATHODE)") (class "Default")
      (node (ref "D7") (pin "1") (pinfunction "CATHODE_1") (pintype "bidirectional"))
      (node (ref "R_CAPACITOR") (pin "2") (pinfunction "2_2") (pintype "passive"))
    )
    (net (code "25") (name "Net-(EPD_C1-Pad1)") (class "Default")
      (node (ref "EPD_C1") (pin "1") (pinfunction "1_1") (pintype "passive"))
      (node (ref "J1") (pin "4") (pinfunction "4_4") (pintype "bidirectional"))
    )
    (net (code "26") (name "Net-(EPD_C2-Pad1)") (class "Default")
      (node (ref "EPD_C2") (pin "1") (pinfunction "1_1") (pintype "passive"))
      (node (ref "J1") (pin "5") (pinfunction "5_5") (pintype "bidirectional"))
    )
    (net (code "27") (name "Net-(EPD_C6-Pad1)") (class "Default")
      (node (ref "EPD_C6") (pin "1") (pinfunction "1_1") (pintype "passive"))
      (node (ref "J1") (pin "18") (pinfunction "18_18") (pintype "bidirectional"))
    )
    (net (code "28") (name "Net-(EPD_C7-Pad1)") (class "Default")
      (node (ref "EPD_C7") (pin "1") (pinfunction "1_1") (pintype "passive"))
      (node (ref "J1") (pin "19") (pinfunction "19_19") (pintype "bidirectional"))
    )
    (net (code "29") (name "Net-(EPD_C8-Pad1)") (class "Default")
      (node (ref "EPD_C8") (pin "1") (pinfunction "1_1") (pintype "passive"))
      (node (ref "J1") (pin "20") (pinfunction "20_20") (pintype "bidirectional"))
    )
    (net (code "30") (name "Net-(EPD_C10-Pad1)") (class "Default")
      (node (ref "EPD_C10") (pin "1") (pinfunction "1_1") (pintype "passive"))
      (node (ref "J1") (pin "22") (pinfunction "22_22") (pintype "bidirectional"))
    )
    (net (code "31") (name "Net-(EPD_C12-Pad1)") (class "Default")
      (node (ref "EPD_C12") (pin "1") (pinfunction "1_1") (pintype "passive"))
      (node (ref "J1") (pin "24") (pinfunction "24_24") (pintype "bidirectional"))
    )
    (net (code "32") (name "Net-(IC1-CT)") (class "Default")
      (node (ref "C_DELAY") (pin "1") (pinfunction "1_1") (pintype "passive"))
      (node (ref "IC1") (pin "5") (pinfunction "CT_5") (pintype "bidirectional"))
    )
    (net (code "33") (name "Net-(J2-PadA5)") (class "Default")
      (node (ref "J2") (pin "A5") (pinfunction "A5_A5") (pintype "bidirectional"))
      (node (ref "R2-USB1") (pin "2") (pinfunction "2_2") (pintype "passive"))
    )
    (net (code "34") (name "Net-(J2-PadB5)") (class "Default")
      (node (ref "J2") (pin "B5") (pinfunction "B5_B5") (pintype "bidirectional"))
      (node (ref "R2-USB") (pin "1") (pinfunction "1_1") (pintype "passive"))
    )
    (net (code "35") (name "Net-(MCP73831-PROG)") (class "Default")
      (node (ref "MCP73831") (pin "5") (pinfunction "PROG_5") (pintype "input"))
      (node (ref "R2_BAT") (pin "2") (pinfunction "2_2") (pintype "passive"))
    )
    (net (code "36") (name "Net-(MCP73831-STAT)") (class "Default")
      (node (ref "MCP73831") (pin "1") (pinfunction "STAT_1") (pintype "output"))
      (node (ref "R1_BAT") (pin "1") (pinfunction "1_1") (pintype "passive"))
    )
    (net (code "37") (name "PREVGH") (class "Default")
      (node (ref "D5") (pin "1") (pinfunction "K_1") (pintype "bidirectional"))
      (node (ref "EPD_C9") (pin "1") (pinfunction "1_1") (pintype "passive"))
      (node (ref "J1") (pin "21") (pinfunction "21_21") (pintype "bidirectional"))
    )
    (net (code "38") (name "PREVGL") (class "Default")
      (node (ref "D3") (pin "2") (pinfunction "A_2") (pintype "bidirectional"))
      (node (ref "EPD_C11") (pin "1") (pinfunction "1_1") (pintype "passive"))
      (node (ref "J1") (pin "23") (pinfunction "23_23") (pintype "bidirectional"))
    )
    (net (code "39") (name "RESE") (class "Default")
      (node (ref "J1") (pin "3") (pinfunction "3_3") (pintype "bidirectional"))
      (node (ref "Q3") (pin "2") (pinfunction "S_2") (pintype "bidirectional"))
      (node (ref "R3") (pin "1") (pinfunction "1_1") (pintype "passive"))
    )
    (net (code "40") (name "RESE'") (class "Default")
      (node (ref "R2") (pin "2") (pinfunction "2_2") (pintype "passive"))
      (node (ref "R3") (pin "2") (pinfunction "2_2") (pintype "passive"))
      (node (ref "SJ1") (pin "2") (pinfunction "2_2") (pintype "passive"))
    )
    (net (code "41") (name "RESET") (class "Default")
      (node (ref "C5") (pin "1") (pinfunction "1_1") (pintype "passive"))
      (node (ref "IC1") (pin "1") (pinfunction "VOUT_1") (pintype "bidirectional"))
      (node (ref "RESET_BUTTON") (pin "3") (pinfunction "3_3") (pintype "passive"))
      (node (ref "RESET_BUTTON") (pin "4") (pinfunction "4_4") (pintype "passive"))
      (node (ref "R_RESET") (pin "2") (pinfunction "2_2") (pintype "passive"))
      (node (ref "U2") (pin "3") (pinfunction "EN_3") (pintype "input"))
    )
    (net (code "42") (name "RTC_RST") (class "Default")
      (node (ref "U2") (pin "16") (pinfunction "IO18_16") (pintype "bidirectional"))
      (node (ref "U3") (pin "4") (pinfunction "~{RST}_4") (pintype "input"))
    )
    (net (code "43") (name "RX") (class "Default")
      (node (ref "RX") (pin "TP") (pinfunction "TP_TP") (pintype "input"))
      (node (ref "U2") (pin "24") (pinfunction "RXD0/GPIO17_24") (pintype "bidirectional"))
    )
    (net (code "44") (name "SCK") (class "Default")
      (node (ref "D10") (pin "2") (pinfunction "2_2") (pintype "passive"))
      (node (ref "J1") (pin "13") (pinfunction "13_13") (pintype "bidirectional"))
      (node (ref "J4") (pin "P5") (pinfunction "CLK_P5") (pintype "bidirectional"))
      (node (ref "R6") (pin "1") (pinfunction "1_1") (pintype "passive"))
      (node (ref "SCK") (pin "TP") (pinfunction "TP_TP") (pintype "input"))
      (node (ref "U1") (pin "6") (pinfunction "CLK_6") (pintype "input"))
      (node (ref "U2") (pin "6") (pinfunction "IO6_6") (pintype "bidirectional"))
    )
    (net (code "45") (name "SCL") (class "Default")
      (node (ref "J3") (pin "4") (pinfunction "4_4") (pintype "passive"))
      (node (ref "R2-PINH") (pin "1") (pinfunction "1_1") (pintype "passive"))
      (node (ref "SENSOR2") (pin "4") (pinfunction "SCK_4") (pintype "input"))
      (node (ref "U2") (pin "20") (pinfunction "IO22_20") (pintype "bidirectional"))
      (node (ref "U3") (pin "16") (pinfunction "SCL_16") (pintype "input"))
      (node (ref "U4") (pin "7") (pinfunction "SCL_7") (pintype "input"))
    )
    (net (code "46") (name "SDA") (class "Default")
      (node (ref "J3") (pin "3") (pinfunction "3_3") (pintype "passive"))
      (node (ref "R1-PINH") (pin "1") (pinfunction "1_1") (pintype "passive"))
      (node (ref "SENSOR2") (pin "3") (pinfunction "SDI_3") (pintype "bidirectional"))
      (node (ref "U2") (pin "19") (pinfunction "IO21_19") (pintype "bidirectional"))
      (node (ref "U3") (pin "15") (pinfunction "SDA_15") (pintype "bidirectional"))
      (node (ref "U4") (pin "8") (pinfunction "SDA_8") (pintype "bidirectional"))
    )
    (net (code "47") (name "SRC") (class "Default")
      (node (ref "C4") (pin "2") (pinfunction "2_2") (pintype "passive"))
      (node (ref "D5") (pin "2") (pinfunction "A_2") (pintype "bidirectional"))
      (node (ref "L1") (pin "1") (pinfunction "1_1") (pintype "passive"))
      (node (ref "Q3") (pin "3") (pinfunction "D_3") (pintype "bidirectional"))
    )
    (net (code "48") (name "SS_SD") (class "Default")
      (node (ref "D8") (pin "2") (pinfunction "2_2") (pintype "passive"))
      (node (ref "J4") (pin "P2") (pinfunction "CD/DAT3_P2") (pintype "bidirectional"))
      (node (ref "R10") (pin "1") (pinfunction "1_1") (pintype "passive"))
      (node (ref "U2") (pin "4") (pinfunction "IO4_4") (pintype "bidirectional"))
    )
    (net (code "49") (name "TX") (class "Default")
      (node (ref "TX") (pin "TP") (pinfunction "TP_TP") (pintype "input"))
      (node (ref "U2") (pin "25") (pinfunction "TXD0/GPIO16_25") (pintype "bidirectional"))
    )
    (net (code "50") (name "USB_D+") (class "Default")
      (node (ref "D1") (pin "1") (pinfunction "I/O1_1_1") (pintype "bidirectional"))
      (node (ref "U2") (pin "14") (pinfunction "IO13_14") (pintype "bidirectional"))
    )
    (net (code "51") (name "USB_D-") (class "Default")
      (node (ref "D1") (pin "3") (pinfunction "I/O2_1_3") (pintype "bidirectional"))
      (node (ref "U2") (pin "13") (pinfunction "IO12_13") (pintype "bidirectional"))
    )
    (net (code "52") (name "VBAT") (class "Default")
      (node (ref "C2_BAT") (pin "1") (pinfunction "1_1") (pintype "passive"))
      (node (ref "MCP73831") (pin "3") (pinfunction "VBAT_3") (pintype "power_in"))
      (node (ref "Q1") (pin "3") (pinfunction "D_3") (pintype "bidirectional"))
      (node (ref "U4") (pin "2") (pinfunction "CELL_2") (pintype "power_in"))
      (node (ref "U4") (pin "3") (pinfunction "VDD_3") (pintype "power_in"))
      (node (ref "VBAT") (pin "TP") (pinfunction "TP_TP") (pintype "input"))
    )
    (net (code "53") (name "VBUS") (class "Default")
      (node (ref "C1_BAT") (pin "1") (pinfunction "1_1") (pintype "passive"))
      (node (ref "C4_USB") (pin "1") (pinfunction "1_1") (pintype "passive"))
      (node (ref "C5_USB") (pin "1") (pinfunction "1_1") (pintype "passive"))
      (node (ref "CHG_LED") (pin "A") (pinfunction "A_A") (pintype "passive"))
      (node (ref "D1") (pin "5") (pinfunction "VBUS_5") (pintype "bidirectional"))
      (node (ref "D2") (pin "2") (pinfunction "ANODE_2") (pintype "bidirectional"))
      (node (ref "MCP73831") (pin "4") (pinfunction "VIN_4") (pintype "power_in"))
      (node (ref "PFMF.050.1") (pin "2") (pinfunction "2_2") (pintype "passive"))
      (node (ref "Q1") (pin "1") (pinfunction "G_1") (pintype "bidirectional"))
      (node (ref "R1_PWRUSB") (pin "2") (pinfunction "2_2") (pintype "passive"))
      (node (ref "VBUS") (pin "TP") (pinfunction "TP_TP") (pintype "input"))
    )
    (net (code "54") (name "VRTC") (class "Default")
      (node (ref "C10_SUPERCAP") (pin "2") (pinfunction "2_2") (pintype "passive"))
      (node (ref "C8") (pin "1") (pinfunction "1_1") (pintype "passive"))
      (node (ref "R_CAPACITOR") (pin "1") (pinfunction "1_1") (pintype "passive"))
      (node (ref "U3") (pin "14") (pinfunction "VBAT_14") (pintype "power_in"))
    )
    (net (code "55") (name "VUSB") (class "Default")
      (node (ref "J2") (pin "A4") (pinfunction "A4_A4") (pintype "bidirectional"))
      (node (ref "J2") (pin "A9") (pinfunction "A9_A9") (pintype "bidirectional"))
      (node (ref "J2") (pin "B4") (pinfunction "B4_B4") (pintype "bidirectional"))
      (node (ref "J2") (pin "B9") (pinfunction "B9_B9") (pintype "bidirectional"))
      (node (ref "PFMF.050.1") (pin "1") (pinfunction "1_1") (pintype "passive"))
    )
    (net (code "56") (name "unconnected-(IC1-NC-Pad4)") (class "Default")
      (node (ref "IC1") (pin "4") (pinfunction "NC_4") (pintype "no_connect"))
    )
    (net (code "57") (name "unconnected-(IC4-NC-Pad4)") (class "Default")
      (node (ref "IC4") (pin "4") (pinfunction "NC_4") (pintype "no_connect"))
    )
    (net (code "58") (name "unconnected-(J1-Pad1)") (class "Default")
      (node (ref "J1") (pin "1") (pinfunction "1_1") (pintype "bidirectional"))
    )
    (net (code "59") (name "unconnected-(J1-Pad6)") (class "Default")
      (node (ref "J1") (pin "6") (pinfunction "6_6") (pintype "bidirectional"))
    )
    (net (code "60") (name "unconnected-(J1-Pad7)") (class "Default")
      (node (ref "J1") (pin "7") (pinfunction "7_7") (pintype "bidirectional"))
    )
    (net (code "61") (name "unconnected-(J2-PadA8)") (class "Default")
      (node (ref "J2") (pin "A8") (pinfunction "A8_A8") (pintype "bidirectional"))
    )
    (net (code "62") (name "unconnected-(J2-PadB8)") (class "Default")
      (node (ref "J2") (pin "B8") (pinfunction "B8_B8") (pintype "bidirectional"))
    )
    (net (code "63") (name "unconnected-(J4-DAT1-PadP8)") (class "Default")
      (node (ref "J4") (pin "P8") (pinfunction "DAT1_P8") (pintype "bidirectional"))
    )
    (net (code "64") (name "unconnected-(J4-DAT2-PadP1)") (class "Default")
      (node (ref "J4") (pin "P1") (pinfunction "DAT2_P1") (pintype "bidirectional"))
    )
    (net (code "65") (name "unconnected-(J4-DETECTION_1-PadS1)") (class "Default")
      (node (ref "J4") (pin "S1") (pinfunction "DETECTION_1_S1") (pintype "bidirectional"))
    )
    (net (code "66") (name "unconnected-(J4-DETECTION_2-PadS2)") (class "Default")
      (node (ref "J4") (pin "S2") (pinfunction "DETECTION_2_S2") (pintype "bidirectional"))
    )
    (net (code "67") (name "unconnected-(U2-NC-Pad22)") (class "Default")
      (node (ref "U2") (pin "22") (pinfunction "NC_22") (pintype "no_connect"))
    )
    (net (code "68") (name "unconnected-(U4-~{ALERT}-Pad5)") (class "Default")
      (node (ref "U4") (pin "5") (pinfunction "~{ALERT}_5") (pintype "output"))
    )
  )
)
